# board_TMC2130.net
KiCad netlist of a schematic drawn in EAGLE
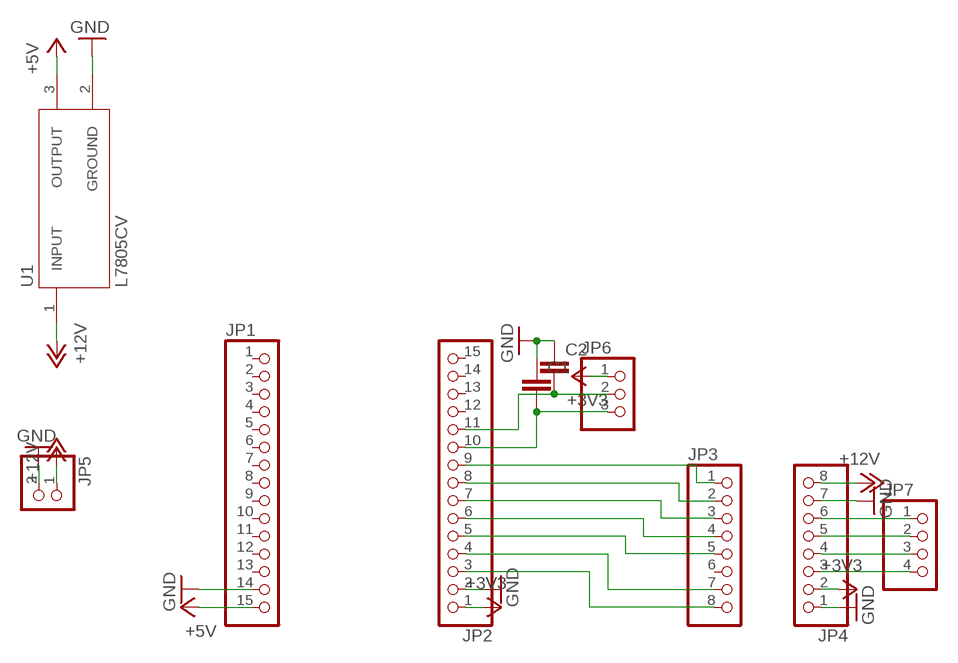
[diagram p0: schematic, sheet 1]

(export (version "E")
  (design (tool "Eeschema 10.0.6"))
  (components
    (comp (ref "C1")
      (value "C-EU025-030X050")
      (footprint "eagle-import:C025-030X050")
      (libsource (lib "eagle-import") (part "C-EU025-030X050"))
    )
    (comp (ref "C2")
      (value "C-EU025-030X050")
      (footprint "eagle-import:C025-030X050")
      (libsource (lib "eagle-import") (part "C-EU025-030X050"))
    )
    (comp (ref "JP1")
      (value "PINHD-1X15")
      (footprint "eagle-import:1X15")
      (libsource (lib "eagle-import") (part "PINHD-1X15"))
    )
    (comp (ref "JP2")
      (value "PINHD-1X15")
      (footprint "eagle-import:1X15")
      (libsource (lib "eagle-import") (part "PINHD-1X15"))
    )
    (comp (ref "JP3")
      (value "PINHD-1X8")
      (footprint "eagle-import:1X08")
      (libsource (lib "eagle-import") (part "PINHD-1X8"))
    )
    (comp (ref "JP4")
      (value "PINHD-1X8")
      (footprint "eagle-import:1X08")
      (libsource (lib "eagle-import") (part "PINHD-1X8"))
    )
    (comp (ref "JP5")
      (value "PINHD-1X2")
      (footprint "eagle-import:1X02")
      (libsource (lib "eagle-import") (part "PINHD-1X2"))
    )
    (comp (ref "JP6")
      (value "PINHD-1X3")
      (footprint "eagle-import:1X03")
      (libsource (lib "eagle-import") (part "PINHD-1X3"))
    )
    (comp (ref "JP7")
      (value "PINHD-1X4")
      (footprint "eagle-import:1X04")
      (libsource (lib "eagle-import") (part "PINHD-1X4"))
    )
    (comp (ref "U1")
      (value "L7805CV")
      (footprint "eagle-import:TO255P1040X460X1968-3")
      (fields (field (name "MF") "STMicroelectronics"))
      (libsource (lib "eagle-import") (part "L7805CV"))
    )
  )
  (nets
    (net (code "1") (name "+3V3") (class "Default")
      (node (ref "JP2") (pin "1") (pinfunction "1_1") (pintype "passive"))
      (node (ref "JP4") (pin "2") (pinfunction "2_2") (pintype "passive"))
      (node (ref "JP6") (pin "1") (pinfunction "1_1") (pintype "passive"))
    )
    (net (code "2") (name "+5V") (class "Default")
      (node (ref "JP1") (pin "15") (pinfunction "15_15") (pintype "passive"))
      (node (ref "U1") (pin "3") (pinfunction "OUTPUT_3") (pintype "output"))
    )
    (net (code "3") (name "+12V") (class "Default")
      (node (ref "JP4") (pin "8") (pinfunction "8_8") (pintype "passive"))
      (node (ref "JP5") (pin "1") (pinfunction "1_1") (pintype "passive"))
      (node (ref "U1") (pin "1") (pinfunction "INPUT_1") (pintype "input"))
    )
    (net (code "4") (name "GND") (class "Default")
      (node (ref "C1") (pin "1") (pinfunction "1_1") (pintype "passive"))
      (node (ref "C2") (pin "1") (pinfunction "1_1") (pintype "passive"))
      (node (ref "JP1") (pin "14") (pinfunction "14_14") (pintype "passive"))
      (node (ref "JP2") (pin "2") (pinfunction "2_2") (pintype "passive"))
      (node (ref "JP4") (pin "1") (pinfunction "1_1") (pintype "passive"))
      (node (ref "JP4") (pin "7") (pinfunction "7_7") (pintype "passive"))
      (node (ref "JP5") (pin "2") (pinfunction "2_2") (pintype "passive"))
      (node (ref "U1") (pin "2") (pinfunction "GROUND_2") (pintype "power_in"))
    )
    (net (code "5") (name "Net-(C1-Pad2)") (class "Default")
      (node (ref "C1") (pin "2") (pinfunction "2_2") (pintype "passive"))
      (node (ref "JP2") (pin "10") (pinfunction "10_10") (pintype "passive"))
      (node (ref "JP6") (pin "3") (pinfunction "3_3") (pintype "passive"))
    )
    (net (code "6") (name "Net-(C2-Pad2)") (class "Default")
      (node (ref "C2") (pin "2") (pinfunction "2_2") (pintype "passive"))
      (node (ref "JP2") (pin "11") (pinfunction "11_11") (pintype "passive"))
      (node (ref "JP6") (pin "2") (pinfunction "2_2") (pintype "passive"))
    )
    (net (code "7") (name "Net-(JP2-Pad3)") (class "Default")
      (node (ref "JP2") (pin "3") (pinfunction "3_3") (pintype "passive"))
      (node (ref "JP3") (pin "8") (pinfunction "8_8") (pintype "passive"))
    )
    (net (code "8") (name "Net-(JP2-Pad4)") (class "Default")
      (node (ref "JP2") (pin "4") (pinfunction "4_4") (pintype "passive"))
      (node (ref "JP3") (pin "7") (pinfunction "7_7") (pintype "passive"))
    )
    (net (code "9") (name "Net-(JP2-Pad5)") (class "Default")
      (node (ref "JP2") (pin "5") (pinfunction "5_5") (pintype "passive"))
      (node (ref "JP3") (pin "5") (pinfunction "5_5") (pintype "passive"))
    )
    (net (code "10") (name "Net-(JP2-Pad6)") (class "Default")
      (node (ref "JP2") (pin "6") (pinfunction "6_6") (pintype "passive"))
      (node (ref "JP3") (pin "4") (pinfunction "4_4") (pintype "passive"))
    )
    (net (code "11") (name "Net-(JP2-Pad7)") (class "Default")
      (node (ref "JP2") (pin "7") (pinfunction "7_7") (pintype "passive"))
      (node (ref "JP3") (pin "3") (pinfunction "3_3") (pintype "passive"))
    )
    (net (code "12") (name "Net-(JP2-Pad8)") (class "Default")
      (node (ref "JP2") (pin "8") (pinfunction "8_8") (pintype "passive"))
      (node (ref "JP3") (pin "2") (pinfunction "2_2") (pintype "passive"))
    )
    (net (code "13") (name "Net-(JP2-Pad9)") (class "Default")
      (node (ref "JP2") (pin "9") (pinfunction "9_9") (pintype "passive"))
      (node (ref "JP3") (pin "1") (pinfunction "1_1") (pintype "passive"))
    )
    (net (code "14") (name "Net-(JP4-Pad3)") (class "Default")
      (node (ref "JP4") (pin "3") (pinfunction "3_3") (pintype "passive"))
      (node (ref "JP7") (pin "4") (pinfunction "4_4") (pintype "passive"))
    )
    (net (code "15") (name "Net-(JP4-Pad4)") (class "Default")
      (node (ref "JP4") (pin "4") (pinfunction "4_4") (pintype "passive"))
      (node (ref "JP7") (pin "3") (pinfunction "3_3") (pintype "passive"))
    )
    (net (code "16") (name "Net-(JP4-Pad5)") (class "Default")
      (node (ref "JP4") (pin "5") (pinfunction "5_5") (pintype "passive"))
      (node (ref "JP7") (pin "2") (pinfunction "2_2") (pintype "passive"))
    )
    (net (code "17") (name "Net-(JP4-Pad6)") (class "Default")
      (node (ref "JP4") (pin "6") (pinfunction "6_6") (pintype "passive"))
      (node (ref "JP7") (pin "1") (pinfunction "1_1") (pintype "passive"))
    )
    (net (code "18") (name "unconnected-(JP1-Pad1)") (class "Default")
      (node (ref "JP1") (pin "1") (pinfunction "1_1") (pintype "passive"))
    )
    (net (code "19") (name "unconnected-(JP1-Pad2)") (class "Default")
      (node (ref "JP1") (pin "2") (pinfunction "2_2") (pintype "passive"))
    )
    (net (code "20") (name "unconnected-(JP1-Pad3)") (class "Default")
      (node (ref "JP1") (pin "3") (pinfunction "3_3") (pintype "passive"))
    )
    (net (code "21") (name "unconnected-(JP1-Pad4)") (class "Default")
      (node (ref "JP1") (pin "4") (pinfunction "4_4") (pintype "passive"))
    )
    (net (code "22") (name "unconnected-(JP1-Pad5)") (class "Default")
      (node (ref "JP1") (pin "5") (pinfunction "5_5") (pintype "passive"))
    )
    (net (code "23") (name "unconnected-(JP1-Pad6)") (class "Default")
      (node (ref "JP1") (pin "6") (pinfunction "6_6") (pintype "passive"))
    )
    (net (code "24") (name "unconnected-(JP1-Pad7)") (class "Default")
      (node (ref "JP1") (pin "7") (pinfunction "7_7") (pintype "passive"))
    )
    (net (code "25") (name "unconnected-(JP1-Pad8)") (class "Default")
      (node (ref "JP1") (pin "8") (pinfunction "8_8") (pintype "passive"))
    )
    (net (code "26") (name "unconnected-(JP1-Pad9)") (class "Default")
      (node (ref "JP1") (pin "9") (pinfunction "9_9") (pintype "passive"))
    )
    (net (code "27") (name "unconnected-(JP1-Pad10)") (class "Default")
      (node (ref "JP1") (pin "10") (pinfunction "10_10") (pintype "passive"))
    )
    (net (code "28") (name "unconnected-(JP1-Pad11)") (class "Default")
      (node (ref "JP1") (pin "11") (pinfunction "11_11") (pintype "passive"))
    )
    (net (code "29") (name "unconnected-(JP1-Pad12)") (class "Default")
      (node (ref "JP1") (pin "12") (pinfunction "12_12") (pintype "passive"))
    )
    (net (code "30") (name "unconnected-(JP1-Pad13)") (class "Default")
      (node (ref "JP1") (pin "13") (pinfunction "13_13") (pintype "passive"))
    )
    (net (code "31") (name "unconnected-(JP2-Pad12)") (class "Default")
      (node (ref "JP2") (pin "12") (pinfunction "12_12") (pintype "passive"))
    )
    (net (code "32") (name "unconnected-(JP2-Pad13)") (class "Default")
      (node (ref "JP2") (pin "13") (pinfunction "13_13") (pintype "passive"))
    )
    (net (code "33") (name "unconnected-(JP2-Pad14)") (class "Default")
      (node (ref "JP2") (pin "14") (pinfunction "14_14") (pintype "passive"))
    )
    (net (code "34") (name "unconnected-(JP2-Pad15)") (class "Default")
      (node (ref "JP2") (pin "15") (pinfunction "15_15") (pintype "passive"))
    )
    (net (code "35") (name "unconnected-(JP3-Pad6)") (class "Default")
      (node (ref "JP3") (pin "6") (pinfunction "6_6") (pintype "passive"))
    )
  )
)
